# protoAndPower.net
KiCad netlist of a schematic drawn in EAGLE
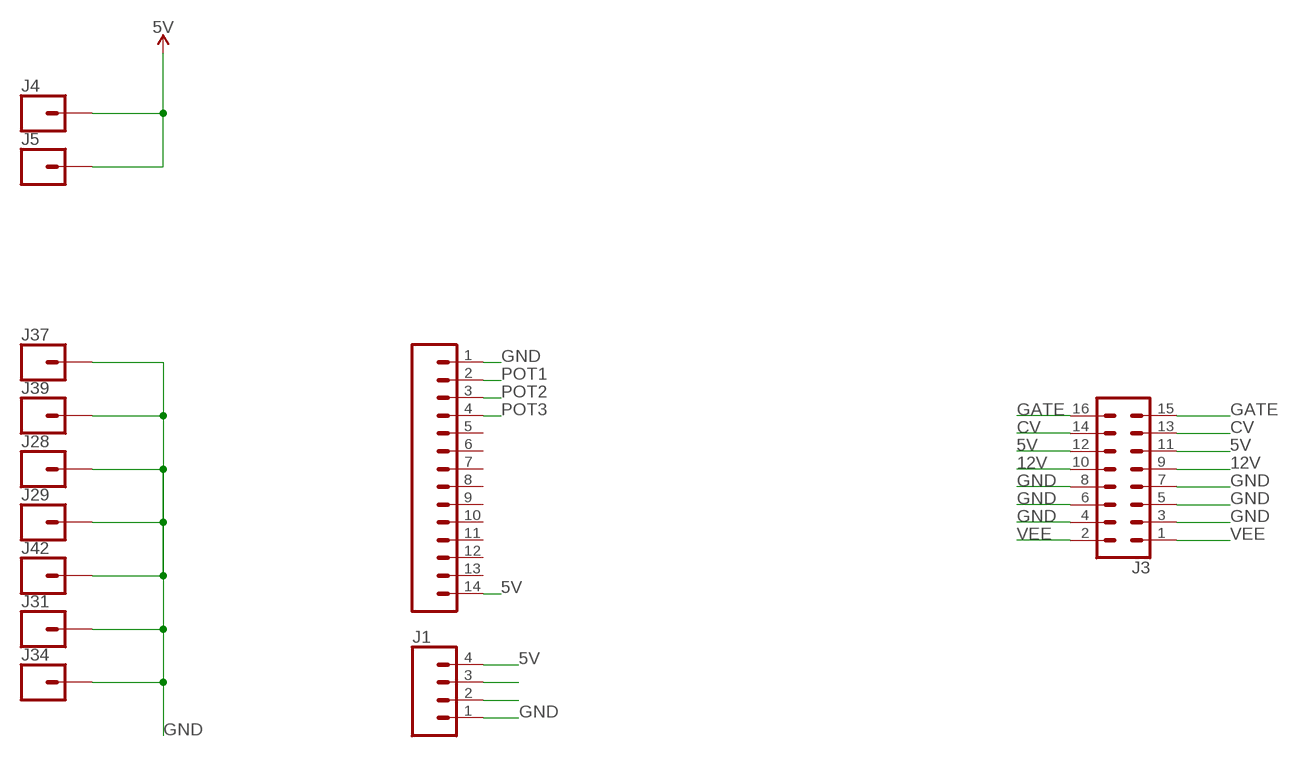
[diagram p0: schematic, sheet 1]

(export (version "E")
  (design (tool "Eeschema 10.0.6"))
  (components
    (comp (ref "J1")
      (value "CONN_04")
      (footprint "eagle-import:1X04")
      (fields (field (name "SPICEPREFIX") "E"))
      (libsource (lib "eagle-import") (part "CONN_04"))
    )
    (comp (ref "J2")
      (value "CONN_14SQUARE")
      (footprint "eagle-import:1X14")
      (fields (field (name "SPICEPREFIX") "X"))
      (libsource (lib "eagle-import") (part "CONN_14SQUARE"))
    )
    (comp (ref "J3")
      (value "CONN_08X2_SHROUD")
      (footprint "eagle-import:2X8-SHROUDED_LOCK")
      (libsource (lib "eagle-import") (part "CONN_08X2_SHROUD"))
    )
    (comp (ref "J4")
      (value "CONN_01")
      (footprint "eagle-import:1X01")
      (libsource (lib "eagle-import") (part "CONN_01"))
    )
    (comp (ref "J5")
      (value "CONN_01")
      (footprint "eagle-import:1X01")
      (libsource (lib "eagle-import") (part "CONN_01"))
    )
    (comp (ref "J28")
      (value "CONN_01")
      (footprint "eagle-import:1X01")
      (libsource (lib "eagle-import") (part "CONN_01"))
    )
    (comp (ref "J29")
      (value "CONN_01")
      (footprint "eagle-import:1X01")
      (libsource (lib "eagle-import") (part "CONN_01"))
    )
    (comp (ref "J31")
      (value "CONN_01")
      (footprint "eagle-import:1X01")
      (libsource (lib "eagle-import") (part "CONN_01"))
    )
    (comp (ref "J34")
      (value "CONN_01")
      (footprint "eagle-import:1X01")
      (libsource (lib "eagle-import") (part "CONN_01"))
    )
    (comp (ref "J37")
      (value "CONN_01")
      (footprint "eagle-import:1X01")
      (libsource (lib "eagle-import") (part "CONN_01"))
    )
    (comp (ref "J39")
      (value "CONN_01")
      (footprint "eagle-import:1X01")
      (libsource (lib "eagle-import") (part "CONN_01"))
    )
    (comp (ref "J42")
      (value "CONN_01")
      (footprint "eagle-import:1X01")
      (libsource (lib "eagle-import") (part "CONN_01"))
    )
  )
  (nets
    (net (code "1") (name "/12V") (class "Default")
      (node (ref "J3") (pin "10") (pinfunction "10_10") (pintype "passive"))
      (node (ref "J3") (pin "9") (pinfunction "9_9") (pintype "passive"))
    )
    (net (code "2") (name "/CV") (class "Default")
      (node (ref "J3") (pin "13") (pinfunction "13_13") (pintype "passive"))
      (node (ref "J3") (pin "14") (pinfunction "14_14") (pintype "passive"))
    )
    (net (code "3") (name "/GATE") (class "Default")
      (node (ref "J3") (pin "15") (pinfunction "15_15") (pintype "passive"))
      (node (ref "J3") (pin "16") (pinfunction "16_16") (pintype "passive"))
    )
    (net (code "4") (name "/GND") (class "Default")
      (node (ref "J1") (pin "1") (pinfunction "1_1") (pintype "passive"))
      (node (ref "J2") (pin "1") (pinfunction "1_1") (pintype "passive"))
      (node (ref "J28") (pin "1") (pinfunction "1_1") (pintype "passive"))
      (node (ref "J29") (pin "1") (pinfunction "1_1") (pintype "passive"))
      (node (ref "J3") (pin "3") (pinfunction "3_3") (pintype "passive"))
      (node (ref "J3") (pin "4") (pinfunction "4_4") (pintype "passive"))
      (node (ref "J3") (pin "5") (pinfunction "5_5") (pintype "passive"))
      (node (ref "J3") (pin "6") (pinfunction "6_6") (pintype "passive"))
      (node (ref "J3") (pin "7") (pinfunction "7_7") (pintype "passive"))
      (node (ref "J3") (pin "8") (pinfunction "8_8") (pintype "passive"))
      (node (ref "J31") (pin "1") (pinfunction "1_1") (pintype "passive"))
      (node (ref "J34") (pin "1") (pinfunction "1_1") (pintype "passive"))
      (node (ref "J37") (pin "1") (pinfunction "1_1") (pintype "passive"))
      (node (ref "J39") (pin "1") (pinfunction "1_1") (pintype "passive"))
      (node (ref "J42") (pin "1") (pinfunction "1_1") (pintype "passive"))
    )
    (net (code "5") (name "/POT1") (class "Default")
      (node (ref "J2") (pin "2") (pinfunction "2_2") (pintype "passive"))
    )
    (net (code "6") (name "/POT2") (class "Default")
      (node (ref "J2") (pin "3") (pinfunction "3_3") (pintype "passive"))
    )
    (net (code "7") (name "/POT3") (class "Default")
      (node (ref "J2") (pin "4") (pinfunction "4_4") (pintype "passive"))
    )
    (net (code "8") (name "/VEE") (class "Default")
      (node (ref "J3") (pin "1") (pinfunction "1_1") (pintype "passive"))
      (node (ref "J3") (pin "2") (pinfunction "2_2") (pintype "passive"))
    )
    (net (code "9") (name "5V") (class "Default")
      (node (ref "J1") (pin "4") (pinfunction "4_4") (pintype "passive"))
      (node (ref "J2") (pin "14") (pinfunction "14_14") (pintype "passive"))
      (node (ref "J3") (pin "11") (pinfunction "11_11") (pintype "passive"))
      (node (ref "J3") (pin "12") (pinfunction "12_12") (pintype "passive"))
      (node (ref "J4") (pin "1") (pinfunction "1_1") (pintype "passive"))
      (node (ref "J5") (pin "1") (pinfunction "1_1") (pintype "passive"))
    )
    (net (code "10") (name "unconnected-(J1-Pad2)") (class "Default")
      (node (ref "J1") (pin "2") (pinfunction "2_2") (pintype "passive"))
    )
    (net (code "11") (name "unconnected-(J1-Pad3)") (class "Default")
      (node (ref "J1") (pin "3") (pinfunction "3_3") (pintype "passive"))
    )
    (net (code "12") (name "unconnected-(J2-Pad5)") (class "Default")
      (node (ref "J2") (pin "5") (pinfunction "5_5") (pintype "passive"))
    )
    (net (code "13") (name "unconnected-(J2-Pad6)") (class "Default")
      (node (ref "J2") (pin "6") (pinfunction "6_6") (pintype "passive"))
    )
    (net (code "14") (name "unconnected-(J2-Pad7)") (class "Default")
      (node (ref "J2") (pin "7") (pinfunction "7_7") (pintype "passive"))
    )
    (net (code "15") (name "unconnected-(J2-Pad8)") (class "Default")
      (node (ref "J2") (pin "8") (pinfunction "8_8") (pintype "passive"))
    )
    (net (code "16") (name "unconnected-(J2-Pad9)") (class "Default")
      (node (ref "J2") (pin "9") (pinfunction "9_9") (pintype "passive"))
    )
    (net (code "17") (name "unconnected-(J2-Pad10)") (class "Default")
      (node (ref "J2") (pin "10") (pinfunction "10_10") (pintype "passive"))
    )
    (net (code "18") (name "unconnected-(J2-Pad11)") (class "Default")
      (node (ref "J2") (pin "11") (pinfunction "11_11") (pintype "passive"))
    )
    (net (code "19") (name "unconnected-(J2-Pad12)") (class "Default")
      (node (ref "J2") (pin "12") (pinfunction "12_12") (pintype "passive"))
    )
    (net (code "20") (name "unconnected-(J2-Pad13)") (class "Default")
      (node (ref "J2") (pin "13") (pinfunction "13_13") (pintype "passive"))
    )
  )
)
